# FlashLight.net
KiCad netlist of a schematic drawn in Altium Designer
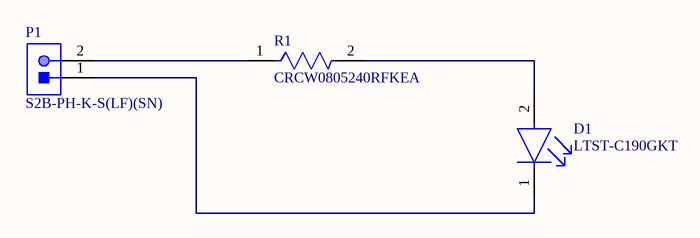
[diagram p0: FlashLight.SchDoc]

(export (version "E")
  (design (tool "Eeschema 10.0.6"))
  (components
    (comp (ref "D1")
      (value "LTST-C190GKT")
      (footprint "FP-LTST-C190GKT-MFG")
      (description "LED GREEN CLEAR CHIP SMD")
      (fields (field (name "VOLTAGE") "2V"))
      (libsource (lib "Altium Content Vault") (part "8706943c75ba83719d021d2fdc84c58"))
    )
    (comp (ref "P1")
      (value "S2B-PH-K-S(LF)(SN)")
      (footprint "JST-S2B-PH-K-S_V")
      (fields (field (name "TOLERANCE") "20%"))
      (libsource (lib "Altium Content Vault") (part "CN-1P-M-R2"))
    )
    (comp (ref "R1")
      (value "CRCW0805240RFKEA")
      (footprint "FP-CRCW0805-e3-MFG")
      (description "RES Thick Film, 240Ω, 1%, 0.125W, 100ppm/°C, 0805")
      (fields (field (name "TOLERANCE") "1%"))
      (libsource (lib "Altium Content Vault") (part "1029c3af85768c4190bb7ad29bc67b5"))
    )
  )
  (nets
    (net (code "1") (name "Net-(D1-A)") (class "Default")
      (node (ref "D1") (pin "2") (pinfunction "A_2") (pintype "passive"))
      (node (ref "R1") (pin "2") (pinfunction "2_2") (pintype "passive"))
    )
    (net (code "2") (name "Net-(D1-C)") (class "Default")
      (node (ref "D1") (pin "1") (pinfunction "C_1") (pintype "passive"))
      (node (ref "P1") (pin "1") (pinfunction "1_1") (pintype "passive"))
    )
    (net (code "3") (name "Net-(P1-Pad2)") (class "Default")
      (node (ref "P1") (pin "2") (pinfunction "2_2") (pintype "passive"))
      (node (ref "R1") (pin "1") (pinfunction "1_1") (pintype "passive"))
    )
  )
)
